# NTC.net
KiCad netlist of a schematic drawn in Altium Designer
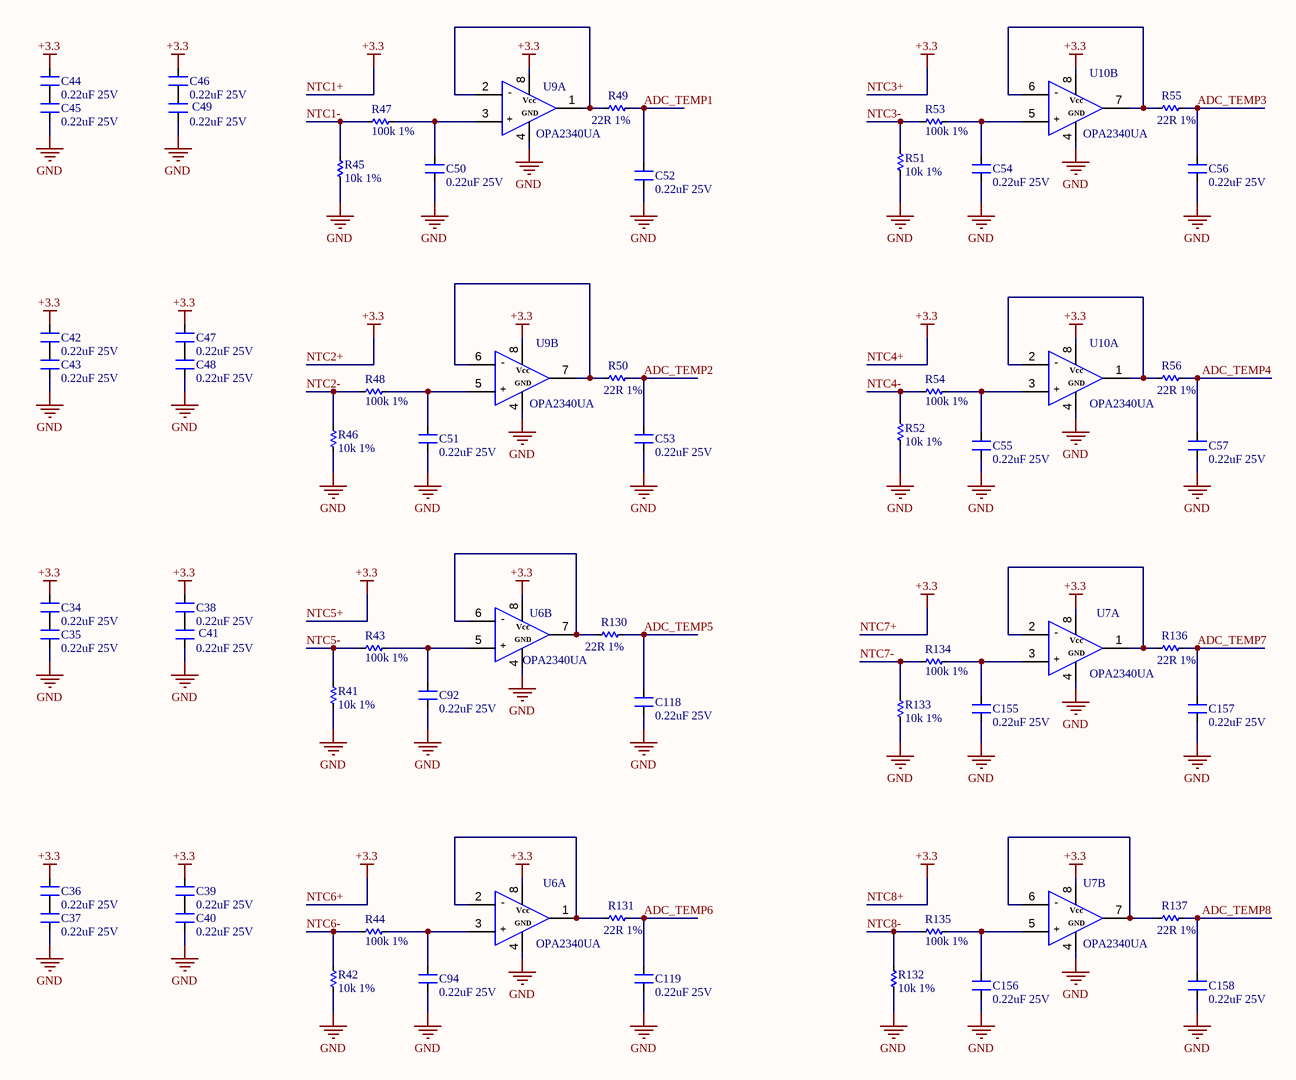
[diagram p0: NTC.SchDoc]

(export (version "E")
  (design (tool "Eeschema 10.0.6"))
  (components
    (comp (ref "C34")
      (value "0.22uF 25V")
      (footprint "CN-SMD-0603-EXP-V101")
      (libsource (lib "Sang_library") (part "Capacitors"))
    )
    (comp (ref "C35")
      (value "0.22uF 25V")
      (footprint "CN-SMD-0603-EXP-V101")
      (libsource (lib "Sang_library") (part "Capacitors"))
    )
    (comp (ref "C36")
      (value "0.22uF 25V")
      (footprint "CN-SMD-0603-EXP-V101")
      (libsource (lib "Sang_library") (part "Capacitors"))
    )
    (comp (ref "C37")
      (value "0.22uF 25V")
      (footprint "CN-SMD-0603-EXP-V101")
      (libsource (lib "Sang_library") (part "Capacitors"))
    )
    (comp (ref "C38")
      (value "0.22uF 25V")
      (footprint "CN-SMD-0603-EXP-V101")
      (libsource (lib "Sang_library") (part "Capacitors"))
    )
    (comp (ref "C39")
      (value "0.22uF 25V")
      (footprint "CN-SMD-0603-EXP-V101")
      (libsource (lib "Sang_library") (part "Capacitors"))
    )
    (comp (ref "C40")
      (value "0.22uF 25V")
      (footprint "CN-SMD-0603-EXP-V101")
      (libsource (lib "Sang_library") (part "Capacitors"))
    )
    (comp (ref "C41")
      (value "0.22uF 25V")
      (footprint "CN-SMD-0603-EXP-V101")
      (libsource (lib "Sang_library") (part "Capacitors"))
    )
    (comp (ref "C42")
      (value "0.22uF 25V")
      (footprint "CN-SMD-0603-EXP-V101")
      (libsource (lib "Sang_library") (part "Capacitors"))
    )
    (comp (ref "C43")
      (value "0.22uF 25V")
      (footprint "CN-SMD-0603-EXP-V101")
      (libsource (lib "Sang_library") (part "Capacitors"))
    )
    (comp (ref "C44")
      (value "0.22uF 25V")
      (footprint "CN-SMD-0603-EXP-V101")
      (libsource (lib "Sang_library") (part "Capacitors"))
    )
    (comp (ref "C45")
      (value "0.22uF 25V")
      (footprint "CN-SMD-0603-EXP-V101")
      (libsource (lib "Sang_library") (part "Capacitors"))
    )
    (comp (ref "C46")
      (value "0.22uF 25V")
      (footprint "CN-SMD-0603-EXP-V101")
      (libsource (lib "Sang_library") (part "Capacitors"))
    )
    (comp (ref "C47")
      (value "0.22uF 25V")
      (footprint "CN-SMD-0603-EXP-V101")
      (libsource (lib "Sang_library") (part "Capacitors"))
    )
    (comp (ref "C48")
      (value "0.22uF 25V")
      (footprint "CN-SMD-0603-EXP-V101")
      (libsource (lib "Sang_library") (part "Capacitors"))
    )
    (comp (ref "C49")
      (value "0.22uF 25V")
      (footprint "CN-SMD-0603-EXP-V101")
      (libsource (lib "Sang_library") (part "Capacitors"))
    )
    (comp (ref "C50")
      (value "0.22uF 25V")
      (footprint "CN-SMD-0603-EXP-V101")
      (libsource (lib "Sang_library") (part "Capacitors"))
    )
    (comp (ref "C51")
      (value "0.22uF 25V")
      (footprint "CN-SMD-0603-EXP-V101")
      (libsource (lib "Sang_library") (part "Capacitors"))
    )
    (comp (ref "C52")
      (value "0.22uF 25V")
      (footprint "CN-SMD-0603-EXP-V101")
      (libsource (lib "Sang_library") (part "Capacitors"))
    )
    (comp (ref "C53")
      (value "0.22uF 25V")
      (footprint "CN-SMD-0603-EXP-V101")
      (libsource (lib "Sang_library") (part "Capacitors"))
    )
    (comp (ref "C54")
      (value "0.22uF 25V")
      (footprint "CN-SMD-0603-EXP-V101")
      (libsource (lib "Sang_library") (part "Capacitors"))
    )
    (comp (ref "C55")
      (value "0.22uF 25V")
      (footprint "CN-SMD-0603-EXP-V101")
      (libsource (lib "Sang_library") (part "Capacitors"))
    )
    (comp (ref "C56")
      (value "0.22uF 25V")
      (footprint "CN-SMD-0603-EXP-V101")
      (libsource (lib "Sang_library") (part "Capacitors"))
    )
    (comp (ref "C57")
      (value "0.22uF 25V")
      (footprint "CN-SMD-0603-EXP-V101")
      (libsource (lib "Sang_library") (part "Capacitors"))
    )
    (comp (ref "C92")
      (value "0.22uF 25V")
      (footprint "CN-SMD-0603-EXP-V101")
      (libsource (lib "Sang_library") (part "Capacitors"))
    )
    (comp (ref "C94")
      (value "0.22uF 25V")
      (footprint "CN-SMD-0603-EXP-V101")
      (libsource (lib "Sang_library") (part "Capacitors"))
    )
    (comp (ref "C118")
      (value "0.22uF 25V")
      (footprint "CN-SMD-0603-EXP-V101")
      (libsource (lib "Sang_library") (part "Capacitors"))
    )
    (comp (ref "C119")
      (value "0.22uF 25V")
      (footprint "CN-SMD-0603-EXP-V101")
      (libsource (lib "Sang_library") (part "Capacitors"))
    )
    (comp (ref "C155")
      (value "0.22uF 25V")
      (footprint "CN-SMD-0603-EXP-V101")
      (libsource (lib "Sang_library") (part "Capacitors"))
    )
    (comp (ref "C156")
      (value "0.22uF 25V")
      (footprint "CN-SMD-0603-EXP-V101")
      (libsource (lib "Sang_library") (part "Capacitors"))
    )
    (comp (ref "C157")
      (value "0.22uF 25V")
      (footprint "CN-SMD-0603-EXP-V101")
      (libsource (lib "Sang_library") (part "Capacitors"))
    )
    (comp (ref "C158")
      (value "0.22uF 25V")
      (footprint "CN-SMD-0603-EXP-V101")
      (libsource (lib "Sang_library") (part "Capacitors"))
    )
    (comp (ref "R41")
      (value "10k 1%")
      (footprint "RES-SMD-0603-EXP-V101")
      (description "SMD")
      (fields
        (field (name "MANUFACTURER") "Generic Components")
        (field (name "PUBLISHER") "Altium Hobart Technology Centre")
      )
      (libsource (lib "Sang_library") (part "Res SMD"))
    )
    (comp (ref "R42")
      (value "10k 1%")
      (footprint "RES-SMD-0603-EXP-V101")
      (description "SMD")
      (fields
        (field (name "MANUFACTURER") "Generic Components")
        (field (name "PUBLISHER") "Altium Hobart Technology Centre")
      )
      (libsource (lib "Sang_library") (part "Res SMD"))
    )
    (comp (ref "R43")
      (value "100k 1%")
      (footprint "RES-SMD-0603-EXP-V101")
      (description "SMD")
      (fields
        (field (name "MANUFACTURER") "Generic Components")
        (field (name "PUBLISHER") "Altium Hobart Technology Centre")
      )
      (libsource (lib "Sang_library") (part "Res SMD"))
    )
    (comp (ref "R44")
      (value "100k 1%")
      (footprint "RES-SMD-0603-EXP-V101")
      (description "SMD")
      (fields
        (field (name "MANUFACTURER") "Generic Components")
        (field (name "PUBLISHER") "Altium Hobart Technology Centre")
      )
      (libsource (lib "Sang_library") (part "Res SMD"))
    )
    (comp (ref "R45")
      (value "10k 1%")
      (footprint "RES-SMD-0603-EXP-V101")
      (description "SMD")
      (fields
        (field (name "MANUFACTURER") "Generic Components")
        (field (name "PUBLISHER") "Altium Hobart Technology Centre")
      )
      (libsource (lib "Sang_library") (part "Res SMD"))
    )
    (comp (ref "R46")
      (value "10k 1%")
      (footprint "RES-SMD-0603-EXP-V101")
      (description "SMD")
      (fields
        (field (name "MANUFACTURER") "Generic Components")
        (field (name "PUBLISHER") "Altium Hobart Technology Centre")
      )
      (libsource (lib "Sang_library") (part "Res SMD"))
    )
    (comp (ref "R47")
      (value "100k 1%")
      (footprint "RES-SMD-0603-EXP-V101")
      (description "SMD")
      (fields
        (field (name "MANUFACTURER") "Generic Components")
        (field (name "PUBLISHER") "Altium Hobart Technology Centre")
      )
      (libsource (lib "Sang_library") (part "Res SMD"))
    )
    (comp (ref "R48")
      (value "100k 1%")
      (footprint "RES-SMD-0603-EXP-V101")
      (description "SMD")
      (fields
        (field (name "MANUFACTURER") "Generic Components")
        (field (name "PUBLISHER") "Altium Hobart Technology Centre")
      )
      (libsource (lib "Sang_library") (part "Res SMD"))
    )
    (comp (ref "R49")
      (value "22R 1%")
      (footprint "RES-SMD-0603-EXP-V101")
      (description "SMD")
      (fields
        (field (name "MANUFACTURER") "Generic Components")
        (field (name "PUBLISHER") "Altium Hobart Technology Centre")
      )
      (libsource (lib "Sang_library") (part "Res SMD"))
    )
    (comp (ref "R50")
      (value "22R 1%")
      (footprint "RES-SMD-0603-EXP-V101")
      (description "SMD")
      (fields
        (field (name "MANUFACTURER") "Generic Components")
        (field (name "PUBLISHER") "Altium Hobart Technology Centre")
      )
      (libsource (lib "Sang_library") (part "Res SMD"))
    )
    (comp (ref "R51")
      (value "10k 1%")
      (footprint "RES-SMD-0603-EXP-V101")
      (description "SMD")
      (fields
        (field (name "MANUFACTURER") "Generic Components")
        (field (name "PUBLISHER") "Altium Hobart Technology Centre")
      )
      (libsource (lib "Sang_library") (part "Res SMD"))
    )
    (comp (ref "R52")
      (value "10k 1%")
      (footprint "RES-SMD-0603-EXP-V101")
      (description "SMD")
      (fields
        (field (name "MANUFACTURER") "Generic Components")
        (field (name "PUBLISHER") "Altium Hobart Technology Centre")
      )
      (libsource (lib "Sang_library") (part "Res SMD"))
    )
    (comp (ref "R53")
      (value "100k 1%")
      (footprint "RES-SMD-0603-EXP-V101")
      (description "SMD")
      (fields
        (field (name "MANUFACTURER") "Generic Components")
        (field (name "PUBLISHER") "Altium Hobart Technology Centre")
      )
      (libsource (lib "Sang_library") (part "Res SMD"))
    )
    (comp (ref "R54")
      (value "100k 1%")
      (footprint "RES-SMD-0603-EXP-V101")
      (description "SMD")
      (fields
        (field (name "MANUFACTURER") "Generic Components")
        (field (name "PUBLISHER") "Altium Hobart Technology Centre")
      )
      (libsource (lib "Sang_library") (part "Res SMD"))
    )
    (comp (ref "R55")
      (value "22R 1%")
      (footprint "RES-SMD-0603-EXP-V101")
      (description "SMD")
      (fields
        (field (name "MANUFACTURER") "Generic Components")
        (field (name "PUBLISHER") "Altium Hobart Technology Centre")
      )
      (libsource (lib "Sang_library") (part "Res SMD"))
    )
    (comp (ref "R56")
      (value "22R 1%")
      (footprint "RES-SMD-0603-EXP-V101")
      (description "SMD")
      (fields
        (field (name "MANUFACTURER") "Generic Components")
        (field (name "PUBLISHER") "Altium Hobart Technology Centre")
      )
      (libsource (lib "Sang_library") (part "Res SMD"))
    )
    (comp (ref "R130")
      (value "22R 1%")
      (footprint "RES-SMD-0603-EXP-V101")
      (description "SMD")
      (fields
        (field (name "MANUFACTURER") "Generic Components")
        (field (name "PUBLISHER") "Altium Hobart Technology Centre")
      )
      (libsource (lib "Sang_library") (part "Res SMD"))
    )
    (comp (ref "R131")
      (value "22R 1%")
      (footprint "RES-SMD-0603-EXP-V101")
      (description "SMD")
      (fields
        (field (name "MANUFACTURER") "Generic Components")
        (field (name "PUBLISHER") "Altium Hobart Technology Centre")
      )
      (libsource (lib "Sang_library") (part "Res SMD"))
    )
    (comp (ref "R132")
      (value "10k 1%")
      (footprint "RES-SMD-0603-EXP-V101")
      (description "SMD")
      (fields
        (field (name "MANUFACTURER") "Generic Components")
        (field (name "PUBLISHER") "Altium Hobart Technology Centre")
      )
      (libsource (lib "Sang_library") (part "Res SMD"))
    )
    (comp (ref "R133")
      (value "10k 1%")
      (footprint "RES-SMD-0603-EXP-V101")
      (description "SMD")
      (fields
        (field (name "MANUFACTURER") "Generic Components")
        (field (name "PUBLISHER") "Altium Hobart Technology Centre")
      )
      (libsource (lib "Sang_library") (part "Res SMD"))
    )
    (comp (ref "R134")
      (value "100k 1%")
      (footprint "RES-SMD-0603-EXP-V101")
      (description "SMD")
      (fields
        (field (name "MANUFACTURER") "Generic Components")
        (field (name "PUBLISHER") "Altium Hobart Technology Centre")
      )
      (libsource (lib "Sang_library") (part "Res SMD"))
    )
    (comp (ref "R135")
      (value "100k 1%")
      (footprint "RES-SMD-0603-EXP-V101")
      (description "SMD")
      (fields
        (field (name "MANUFACTURER") "Generic Components")
        (field (name "PUBLISHER") "Altium Hobart Technology Centre")
      )
      (libsource (lib "Sang_library") (part "Res SMD"))
    )
    (comp (ref "R136")
      (value "22R 1%")
      (footprint "RES-SMD-0603-EXP-V101")
      (description "SMD")
      (fields
        (field (name "MANUFACTURER") "Generic Components")
        (field (name "PUBLISHER") "Altium Hobart Technology Centre")
      )
      (libsource (lib "Sang_library") (part "Res SMD"))
    )
    (comp (ref "R137")
      (value "22R 1%")
      (footprint "RES-SMD-0603-EXP-V101")
      (description "SMD")
      (fields
        (field (name "MANUFACTURER") "Generic Components")
        (field (name "PUBLISHER") "Altium Hobart Technology Centre")
      )
      (libsource (lib "Sang_library") (part "Res SMD"))
    )
    (comp (ref "U6")
      (value "OPA2340UA")
      (footprint "SO8")
      (libsource (lib "Sang_library") (part "OPA2340UA/2K5"))
    )
    (comp (ref "U7")
      (value "OPA2340UA")
      (footprint "SO8")
      (libsource (lib "Sang_library") (part "OPA2340UA/2K5"))
    )
    (comp (ref "U9")
      (value "OPA2340UA")
      (footprint "SO8")
      (libsource (lib "Sang_library") (part "OPA2340UA/2K5"))
    )
    (comp (ref "U10")
      (value "OPA2340UA")
      (footprint "SO8")
      (libsource (lib "Sang_library") (part "OPA2340UA/2K5"))
    )
  )
  (nets
    (net (code "1") (name "+3.3") (class "Default")
      (node (ref "C34") (pin "2") (pinfunction "2_2") (pintype "passive"))
      (node (ref "C36") (pin "2") (pinfunction "2_2") (pintype "passive"))
      (node (ref "C38") (pin "2") (pinfunction "2_2") (pintype "passive"))
      (node (ref "C39") (pin "2") (pinfunction "2_2") (pintype "passive"))
      (node (ref "C42") (pin "2") (pinfunction "2_2") (pintype "passive"))
      (node (ref "C44") (pin "2") (pinfunction "2_2") (pintype "passive"))
      (node (ref "C46") (pin "2") (pinfunction "2_2") (pintype "passive"))
      (node (ref "C47") (pin "2") (pinfunction "2_2") (pintype "passive"))
      (node (ref "U10") (pin "8") (pinfunction "8_8") (pintype "passive"))
      (node (ref "U6") (pin "8") (pinfunction "8_8") (pintype "passive"))
      (node (ref "U7") (pin "8") (pinfunction "8_8") (pintype "passive"))
      (node (ref "U9") (pin "8") (pinfunction "8_8") (pintype "passive"))
    )
    (net (code "2") (name "/ADC_TEMP1") (class "Default")
      (node (ref "C52") (pin "2") (pinfunction "2_2") (pintype "passive"))
      (node (ref "R49") (pin "2") (pinfunction "2_2") (pintype "passive"))
    )
    (net (code "3") (name "/ADC_TEMP2") (class "Default")
      (node (ref "C53") (pin "2") (pinfunction "2_2") (pintype "passive"))
      (node (ref "R50") (pin "2") (pinfunction "2_2") (pintype "passive"))
    )
    (net (code "4") (name "/ADC_TEMP3") (class "Default")
      (node (ref "C56") (pin "2") (pinfunction "2_2") (pintype "passive"))
      (node (ref "R55") (pin "2") (pinfunction "2_2") (pintype "passive"))
    )
    (net (code "5") (name "/ADC_TEMP4") (class "Default")
      (node (ref "C57") (pin "2") (pinfunction "2_2") (pintype "passive"))
      (node (ref "R56") (pin "2") (pinfunction "2_2") (pintype "passive"))
    )
    (net (code "6") (name "/ADC_TEMP5") (class "Default")
      (node (ref "C118") (pin "2") (pinfunction "2_2") (pintype "passive"))
      (node (ref "R130") (pin "2") (pinfunction "2_2") (pintype "passive"))
    )
    (net (code "7") (name "/ADC_TEMP6") (class "Default")
      (node (ref "C119") (pin "2") (pinfunction "2_2") (pintype "passive"))
      (node (ref "R131") (pin "2") (pinfunction "2_2") (pintype "passive"))
    )
    (net (code "8") (name "/ADC_TEMP7") (class "Default")
      (node (ref "C157") (pin "2") (pinfunction "2_2") (pintype "passive"))
      (node (ref "R136") (pin "2") (pinfunction "2_2") (pintype "passive"))
    )
    (net (code "9") (name "/ADC_TEMP8") (class "Default")
      (node (ref "C158") (pin "2") (pinfunction "2_2") (pintype "passive"))
      (node (ref "R137") (pin "2") (pinfunction "2_2") (pintype "passive"))
    )
    (net (code "10") (name "/NTC1-") (class "Default")
      (node (ref "R45") (pin "1") (pinfunction "1_1") (pintype "passive"))
      (node (ref "R47") (pin "1") (pinfunction "1_1") (pintype "passive"))
    )
    (net (code "11") (name "/NTC2-") (class "Default")
      (node (ref "R46") (pin "1") (pinfunction "1_1") (pintype "passive"))
      (node (ref "R48") (pin "1") (pinfunction "1_1") (pintype "passive"))
    )
    (net (code "12") (name "/NTC3-") (class "Default")
      (node (ref "R51") (pin "1") (pinfunction "1_1") (pintype "passive"))
      (node (ref "R53") (pin "1") (pinfunction "1_1") (pintype "passive"))
    )
    (net (code "13") (name "/NTC4-") (class "Default")
      (node (ref "R52") (pin "1") (pinfunction "1_1") (pintype "passive"))
      (node (ref "R54") (pin "1") (pinfunction "1_1") (pintype "passive"))
    )
    (net (code "14") (name "/NTC5-") (class "Default")
      (node (ref "R41") (pin "1") (pinfunction "1_1") (pintype "passive"))
      (node (ref "R43") (pin "1") (pinfunction "1_1") (pintype "passive"))
    )
    (net (code "15") (name "/NTC6-") (class "Default")
      (node (ref "R42") (pin "1") (pinfunction "1_1") (pintype "passive"))
      (node (ref "R44") (pin "1") (pinfunction "1_1") (pintype "passive"))
    )
    (net (code "16") (name "/NTC7-") (class "Default")
      (node (ref "R133") (pin "1") (pinfunction "1_1") (pintype "passive"))
      (node (ref "R134") (pin "1") (pinfunction "1_1") (pintype "passive"))
    )
    (net (code "17") (name "/NTC8-") (class "Default")
      (node (ref "R132") (pin "1") (pinfunction "1_1") (pintype "passive"))
      (node (ref "R135") (pin "1") (pinfunction "1_1") (pintype "passive"))
    )
    (net (code "18") (name "GND") (class "Default")
      (node (ref "C118") (pin "1") (pinfunction "1_1") (pintype "passive"))
      (node (ref "C119") (pin "1") (pinfunction "1_1") (pintype "passive"))
      (node (ref "C155") (pin "1") (pinfunction "1_1") (pintype "passive"))
      (node (ref "C156") (pin "1") (pinfunction "1_1") (pintype "passive"))
      (node (ref "C157") (pin "1") (pinfunction "1_1") (pintype "passive"))
      (node (ref "C158") (pin "1") (pinfunction "1_1") (pintype "passive"))
      (node (ref "C35") (pin "1") (pinfunction "1_1") (pintype "passive"))
      (node (ref "C37") (pin "1") (pinfunction "1_1") (pintype "passive"))
      (node (ref "C40") (pin "1") (pinfunction "1_1") (pintype "passive"))
      (node (ref "C41") (pin "1") (pinfunction "1_1") (pintype "passive"))
      (node (ref "C43") (pin "1") (pinfunction "1_1") (pintype "passive"))
      (node (ref "C45") (pin "1") (pinfunction "1_1") (pintype "passive"))
      (node (ref "C48") (pin "1") (pinfunction "1_1") (pintype "passive"))
      (node (ref "C49") (pin "1") (pinfunction "1_1") (pintype "passive"))
      (node (ref "C50") (pin "1") (pinfunction "1_1") (pintype "passive"))
      (node (ref "C51") (pin "1") (pinfunction "1_1") (pintype "passive"))
      (node (ref "C52") (pin "1") (pinfunction "1_1") (pintype "passive"))
      (node (ref "C53") (pin "1") (pinfunction "1_1") (pintype "passive"))
      (node (ref "C54") (pin "1") (pinfunction "1_1") (pintype "passive"))
      (node (ref "C55") (pin "1") (pinfunction "1_1") (pintype "passive"))
      (node (ref "C56") (pin "1") (pinfunction "1_1") (pintype "passive"))
      (node (ref "C57") (pin "1") (pinfunction "1_1") (pintype "passive"))
      (node (ref "C92") (pin "1") (pinfunction "1_1") (pintype "passive"))
      (node (ref "C94") (pin "1") (pinfunction "1_1") (pintype "passive"))
      (node (ref "R132") (pin "2") (pinfunction "2_2") (pintype "passive"))
      (node (ref "R133") (pin "2") (pinfunction "2_2") (pintype "passive"))
      (node (ref "R41") (pin "2") (pinfunction "2_2") (pintype "passive"))
      (node (ref "R42") (pin "2") (pinfunction "2_2") (pintype "passive"))
      (node (ref "R45") (pin "2") (pinfunction "2_2") (pintype "passive"))
      (node (ref "R46") (pin "2") (pinfunction "2_2") (pintype "passive"))
      (node (ref "R51") (pin "2") (pinfunction "2_2") (pintype "passive"))
      (node (ref "R52") (pin "2") (pinfunction "2_2") (pintype "passive"))
      (node (ref "U10") (pin "4") (pinfunction "4_4") (pintype "passive"))
      (node (ref "U6") (pin "4") (pinfunction "4_4") (pintype "passive"))
      (node (ref "U7") (pin "4") (pinfunction "4_4") (pintype "passive"))
      (node (ref "U9") (pin "4") (pinfunction "4_4") (pintype "passive"))
    )
    (net (code "19") (name "Net-(C34-Pad1)") (class "Default")
      (node (ref "C34") (pin "1") (pinfunction "1_1") (pintype "passive"))
      (node (ref "C35") (pin "2") (pinfunction "2_2") (pintype "passive"))
    )
    (net (code "20") (name "Net-(C36-Pad1)") (class "Default")
      (node (ref "C36") (pin "1") (pinfunction "1_1") (pintype "passive"))
      (node (ref "C37") (pin "2") (pinfunction "2_2") (pintype "passive"))
    )
    (net (code "21") (name "Net-(C38-Pad1)") (class "Default")
      (node (ref "C38") (pin "1") (pinfunction "1_1") (pintype "passive"))
      (node (ref "C41") (pin "2") (pinfunction "2_2") (pintype "passive"))
    )
    (net (code "22") (name "Net-(C39-Pad1)") (class "Default")
      (node (ref "C39") (pin "1") (pinfunction "1_1") (pintype "passive"))
      (node (ref "C40") (pin "2") (pinfunction "2_2") (pintype "passive"))
    )
    (net (code "23") (name "Net-(C42-Pad1)") (class "Default")
      (node (ref "C42") (pin "1") (pinfunction "1_1") (pintype "passive"))
      (node (ref "C43") (pin "2") (pinfunction "2_2") (pintype "passive"))
    )
    (net (code "24") (name "Net-(C44-Pad1)") (class "Default")
      (node (ref "C44") (pin "1") (pinfunction "1_1") (pintype "passive"))
      (node (ref "C45") (pin "2") (pinfunction "2_2") (pintype "passive"))
    )
    (net (code "25") (name "Net-(C46-Pad1)") (class "Default")
      (node (ref "C46") (pin "1") (pinfunction "1_1") (pintype "passive"))
      (node (ref "C49") (pin "2") (pinfunction "2_2") (pintype "passive"))
    )
    (net (code "26") (name "Net-(C47-Pad1)") (class "Default")
      (node (ref "C47") (pin "1") (pinfunction "1_1") (pintype "passive"))
      (node (ref "C48") (pin "2") (pinfunction "2_2") (pintype "passive"))
    )
    (net (code "27") (name "Net-(C50-Pad2)") (class "Default")
      (node (ref "C50") (pin "2") (pinfunction "2_2") (pintype "passive"))
      (node (ref "R47") (pin "2") (pinfunction "2_2") (pintype "passive"))
      (node (ref "U9") (pin "3") (pinfunction "3_3") (pintype "passive"))
    )
    (net (code "28") (name "Net-(C51-Pad2)") (class "Default")
      (node (ref "C51") (pin "2") (pinfunction "2_2") (pintype "passive"))
      (node (ref "R48") (pin "2") (pinfunction "2_2") (pintype "passive"))
      (node (ref "U9") (pin "5") (pinfunction "5_5") (pintype "passive"))
    )
    (net (code "29") (name "Net-(C54-Pad2)") (class "Default")
      (node (ref "C54") (pin "2") (pinfunction "2_2") (pintype "passive"))
      (node (ref "R53") (pin "2") (pinfunction "2_2") (pintype "passive"))
      (node (ref "U10") (pin "5") (pinfunction "5_5") (pintype "passive"))
    )
    (net (code "30") (name "Net-(C55-Pad2)") (class "Default")
      (node (ref "C55") (pin "2") (pinfunction "2_2") (pintype "passive"))
      (node (ref "R54") (pin "2") (pinfunction "2_2") (pintype "passive"))
      (node (ref "U10") (pin "3") (pinfunction "3_3") (pintype "passive"))
    )
    (net (code "31") (name "Net-(C92-Pad2)") (class "Default")
      (node (ref "C92") (pin "2") (pinfunction "2_2") (pintype "passive"))
      (node (ref "R43") (pin "2") (pinfunction "2_2") (pintype "passive"))
      (node (ref "U6") (pin "5") (pinfunction "5_5") (pintype "passive"))
    )
    (net (code "32") (name "Net-(C94-Pad2)") (class "Default")
      (node (ref "C94") (pin "2") (pinfunction "2_2") (pintype "passive"))
      (node (ref "R44") (pin "2") (pinfunction "2_2") (pintype "passive"))
      (node (ref "U6") (pin "3") (pinfunction "3_3") (pintype "passive"))
    )
    (net (code "33") (name "Net-(C155-Pad2)") (class "Default")
      (node (ref "C155") (pin "2") (pinfunction "2_2") (pintype "passive"))
      (node (ref "R134") (pin "2") (pinfunction "2_2") (pintype "passive"))
      (node (ref "U7") (pin "3") (pinfunction "3_3") (pintype "passive"))
    )
    (net (code "34") (name "Net-(C156-Pad2)") (class "Default")
      (node (ref "C156") (pin "2") (pinfunction "2_2") (pintype "passive"))
      (node (ref "R135") (pin "2") (pinfunction "2_2") (pintype "passive"))
      (node (ref "U7") (pin "5") (pinfunction "5_5") (pintype "passive"))
    )
    (net (code "35") (name "Net-(R49-Pad1)") (class "Default")
      (node (ref "R49") (pin "1") (pinfunction "1_1") (pintype "passive"))
      (node (ref "U9") (pin "1") (pinfunction "1_1") (pintype "passive"))
      (node (ref "U9") (pin "2") (pinfunction "2_2") (pintype "passive"))
    )
    (net (code "36") (name "Net-(R50-Pad1)") (class "Default")
      (node (ref "R50") (pin "1") (pinfunction "1_1") (pintype "passive"))
      (node (ref "U9") (pin "6") (pinfunction "6_6") (pintype "passive"))
      (node (ref "U9") (pin "7") (pinfunction "7_7") (pintype "passive"))
    )
    (net (code "37") (name "Net-(R55-Pad1)") (class "Default")
      (node (ref "R55") (pin "1") (pinfunction "1_1") (pintype "passive"))
      (node (ref "U10") (pin "6") (pinfunction "6_6") (pintype "passive"))
      (node (ref "U10") (pin "7") (pinfunction "7_7") (pintype "passive"))
    )
    (net (code "38") (name "Net-(R56-Pad1)") (class "Default")
      (node (ref "R56") (pin "1") (pinfunction "1_1") (pintype "passive"))
      (node (ref "U10") (pin "1") (pinfunction "1_1") (pintype "passive"))
      (node (ref "U10") (pin "2") (pinfunction "2_2") (pintype "passive"))
    )
    (net (code "39") (name "Net-(R130-Pad1)") (class "Default")
      (node (ref "R130") (pin "1") (pinfunction "1_1") (pintype "passive"))
      (node (ref "U6") (pin "6") (pinfunction "6_6") (pintype "passive"))
      (node (ref "U6") (pin "7") (pinfunction "7_7") (pintype "passive"))
    )
    (net (code "40") (name "Net-(R131-Pad1)") (class "Default")
      (node (ref "R131") (pin "1") (pinfunction "1_1") (pintype "passive"))
      (node (ref "U6") (pin "1") (pinfunction "1_1") (pintype "passive"))
      (node (ref "U6") (pin "2") (pinfunction "2_2") (pintype "passive"))
    )
    (net (code "41") (name "Net-(R136-Pad1)") (class "Default")
      (node (ref "R136") (pin "1") (pinfunction "1_1") (pintype "passive"))
      (node (ref "U7") (pin "1") (pinfunction "1_1") (pintype "passive"))
      (node (ref "U7") (pin "2") (pinfunction "2_2") (pintype "passive"))
    )
    (net (code "42") (name "Net-(R137-Pad1)") (class "Default")
      (node (ref "R137") (pin "1") (pinfunction "1_1") (pintype "passive"))
      (node (ref "U7") (pin "6") (pinfunction "6_6") (pintype "passive"))
      (node (ref "U7") (pin "7") (pinfunction "7_7") (pintype "passive"))
    )
  )
)
